# taillights3.net
KiCad netlist of a schematic drawn in EAGLE
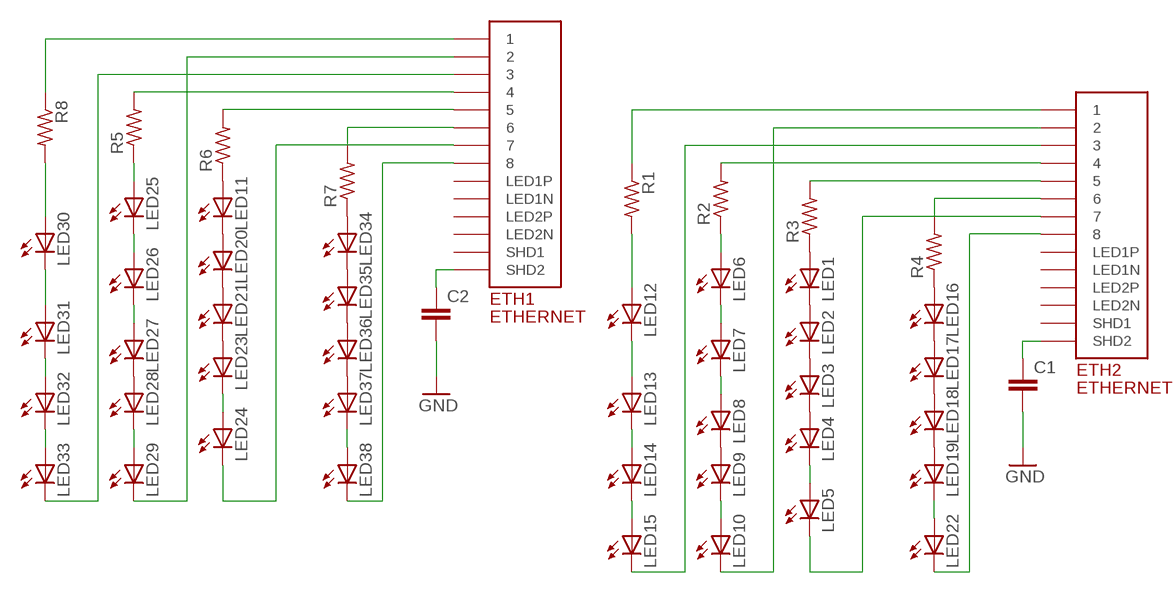
[diagram p0: schematic, sheet 1]

(export (version "E")
  (design (tool "Eeschema 10.0.6"))
  (components
    (comp (ref "C1")
      (value "C2,5-3")
      (footprint "eagle-import:C2.5-3")
      (libsource (lib "eagle-import") (part "C2,5-3"))
    )
    (comp (ref "C2")
      (value "C2,5-3")
      (footprint "eagle-import:C2.5-3")
      (libsource (lib "eagle-import") (part "C2,5-3"))
    )
    (comp (ref "ETH1")
      (value "ETHERNET")
      (footprint "eagle-import:A122645-ND")
      (libsource (lib "eagle-import") (part "ETHERNET"))
    )
    (comp (ref "ETH2")
      (value "ETHERNET")
      (footprint "eagle-import:A122645-ND")
      (libsource (lib "eagle-import") (part "ETHERNET"))
    )
    (comp (ref "LED1")
      (value "LED")
      (footprint "eagle-import:SMARTLED-TTW")
      (libsource (lib "eagle-import") (part "LED"))
    )
    (comp (ref "LED2")
      (value "LED")
      (footprint "eagle-import:SMARTLED-TTW")
      (libsource (lib "eagle-import") (part "LED"))
    )
    (comp (ref "LED3")
      (value "LED")
      (footprint "eagle-import:SMARTLED-TTW")
      (libsource (lib "eagle-import") (part "LED"))
    )
    (comp (ref "LED4")
      (value "LED")
      (footprint "eagle-import:SMARTLED-TTW")
      (libsource (lib "eagle-import") (part "LED"))
    )
    (comp (ref "LED5")
      (value "LED")
      (footprint "eagle-import:SMARTLED-TTW")
      (libsource (lib "eagle-import") (part "LED"))
    )
    (comp (ref "LED6")
      (value "LED")
      (footprint "eagle-import:SMARTLED-TTW")
      (libsource (lib "eagle-import") (part "LED"))
    )
    (comp (ref "LED7")
      (value "LED")
      (footprint "eagle-import:SMARTLED-TTW")
      (libsource (lib "eagle-import") (part "LED"))
    )
    (comp (ref "LED8")
      (value "LED")
      (footprint "eagle-import:SMARTLED-TTW")
      (libsource (lib "eagle-import") (part "LED"))
    )
    (comp (ref "LED9")
      (value "LED")
      (footprint "eagle-import:SMARTLED-TTW")
      (libsource (lib "eagle-import") (part "LED"))
    )
    (comp (ref "LED10")
      (value "LED")
      (footprint "eagle-import:SMARTLED-TTW")
      (libsource (lib "eagle-import") (part "LED"))
    )
    (comp (ref "LED11")
      (value "LED")
      (footprint "eagle-import:SMARTLED-TTW")
      (libsource (lib "eagle-import") (part "LED"))
    )
    (comp (ref "LED12")
      (value "LED")
      (footprint "eagle-import:SMARTLED-TTW")
      (libsource (lib "eagle-import") (part "LED"))
    )
    (comp (ref "LED13")
      (value "LED")
      (footprint "eagle-import:SMARTLED-TTW")
      (libsource (lib "eagle-import") (part "LED"))
    )
    (comp (ref "LED14")
      (value "LED")
      (footprint "eagle-import:SMARTLED-TTW")
      (libsource (lib "eagle-import") (part "LED"))
    )
    (comp (ref "LED15")
      (value "LED")
      (footprint "eagle-import:SMARTLED-TTW")
      (libsource (lib "eagle-import") (part "LED"))
    )
    (comp (ref "LED16")
      (value "LED")
      (footprint "eagle-import:SMARTLED-TTW")
      (libsource (lib "eagle-import") (part "LED"))
    )
    (comp (ref "LED17")
      (value "LED")
      (footprint "eagle-import:SMARTLED-TTW")
      (libsource (lib "eagle-import") (part "LED"))
    )
    (comp (ref "LED18")
      (value "LED")
      (footprint "eagle-import:SMARTLED-TTW")
      (libsource (lib "eagle-import") (part "LED"))
    )
    (comp (ref "LED19")
      (value "LED")
      (footprint "eagle-import:SMARTLED-TTW")
      (libsource (lib "eagle-import") (part "LED"))
    )
    (comp (ref "LED20")
      (value "LED")
      (footprint "eagle-import:SMARTLED-TTW")
      (libsource (lib "eagle-import") (part "LED"))
    )
    (comp (ref "LED21")
      (value "LED")
      (footprint "eagle-import:SMARTLED-TTW")
      (libsource (lib "eagle-import") (part "LED"))
    )
    (comp (ref "LED22")
      (value "LED")
      (footprint "eagle-import:SMARTLED-TTW")
      (libsource (lib "eagle-import") (part "LED"))
    )
    (comp (ref "LED23")
      (value "LED")
      (footprint "eagle-import:SMARTLED-TTW")
      (libsource (lib "eagle-import") (part "LED"))
    )
    (comp (ref "LED24")
      (value "LED")
      (footprint "eagle-import:SMARTLED-TTW")
      (libsource (lib "eagle-import") (part "LED"))
    )
    (comp (ref "LED25")
      (value "LED")
      (footprint "eagle-import:SMARTLED-TTW")
      (libsource (lib "eagle-import") (part "LED"))
    )
    (comp (ref "LED26")
      (value "LED")
      (footprint "eagle-import:SMARTLED-TTW")
      (libsource (lib "eagle-import") (part "LED"))
    )
    (comp (ref "LED27")
      (value "LED")
      (footprint "eagle-import:SMARTLED-TTW")
      (libsource (lib "eagle-import") (part "LED"))
    )
    (comp (ref "LED28")
      (value "LED")
      (footprint "eagle-import:SMARTLED-TTW")
      (libsource (lib "eagle-import") (part "LED"))
    )
    (comp (ref "LED29")
      (value "LED")
      (footprint "eagle-import:SMARTLED-TTW")
      (libsource (lib "eagle-import") (part "LED"))
    )
    (comp (ref "LED30")
      (value "LED")
      (footprint "eagle-import:SMARTLED-TTW")
      (libsource (lib "eagle-import") (part "LED"))
    )
    (comp (ref "LED31")
      (value "LED")
      (footprint "eagle-import:SMARTLED-TTW")
      (libsource (lib "eagle-import") (part "LED"))
    )
    (comp (ref "LED32")
      (value "LED")
      (footprint "eagle-import:SMARTLED-TTW")
      (libsource (lib "eagle-import") (part "LED"))
    )
    (comp (ref "LED33")
      (value "LED")
      (footprint "eagle-import:SMARTLED-TTW")
      (libsource (lib "eagle-import") (part "LED"))
    )
    (comp (ref "LED34")
      (value "LED")
      (footprint "eagle-import:SMARTLED-TTW")
      (libsource (lib "eagle-import") (part "LED"))
    )
    (comp (ref "LED35")
      (value "LED")
      (footprint "eagle-import:SMARTLED-TTW")
      (libsource (lib "eagle-import") (part "LED"))
    )
    (comp (ref "LED36")
      (value "LED")
      (footprint "eagle-import:SMARTLED-TTW")
      (libsource (lib "eagle-import") (part "LED"))
    )
    (comp (ref "LED37")
      (value "LED")
      (footprint "eagle-import:SMARTLED-TTW")
      (libsource (lib "eagle-import") (part "LED"))
    )
    (comp (ref "LED38")
      (value "LED")
      (footprint "eagle-import:SMARTLED-TTW")
      (libsource (lib "eagle-import") (part "LED"))
    )
    (comp (ref "R1")
      (value "R-US_0204/5")
      (footprint "eagle-import:0204_5")
      (libsource (lib "eagle-import") (part "R-US_0204/5"))
    )
    (comp (ref "R2")
      (value "R-US_0204/2V")
      (footprint "eagle-import:0204V")
      (libsource (lib "eagle-import") (part "R-US_0204/2V"))
    )
    (comp (ref "R3")
      (value "R-US_0204/2V")
      (footprint "eagle-import:0204V")
      (libsource (lib "eagle-import") (part "R-US_0204/2V"))
    )
    (comp (ref "R4")
      (value "R-US_0204/2V")
      (footprint "eagle-import:0204V")
      (libsource (lib "eagle-import") (part "R-US_0204/2V"))
    )
    (comp (ref "R5")
      (value "R-US_0204/2V")
      (footprint "eagle-import:0204V")
      (libsource (lib "eagle-import") (part "R-US_0204/2V"))
    )
    (comp (ref "R6")
      (value "R-US_0204/2V")
      (footprint "eagle-import:0204V")
      (libsource (lib "eagle-import") (part "R-US_0204/2V"))
    )
    (comp (ref "R7")
      (value "R-US_0204/2V")
      (footprint "eagle-import:0204V")
      (libsource (lib "eagle-import") (part "R-US_0204/2V"))
    )
    (comp (ref "R8")
      (value "R-US_0204/5")
      (footprint "eagle-import:0204_5")
      (libsource (lib "eagle-import") (part "R-US_0204/5"))
    )
  )
  (nets
    (net (code "1") (name "GND") (class "Default")
      (node (ref "C1") (pin "2") (pinfunction "2_2") (pintype "passive"))
      (node (ref "C2") (pin "2") (pinfunction "2_2") (pintype "passive"))
    )
    (net (code "2") (name "Net-(ETH1-1)") (class "Default")
      (node (ref "ETH1") (pin "P$1") (pinfunction "1_P$1") (pintype "bidirectional"))
      (node (ref "R8") (pin "1") (pinfunction "1_1") (pintype "passive"))
    )
    (net (code "3") (name "Net-(ETH1-2)") (class "Default")
      (node (ref "ETH1") (pin "P$2") (pinfunction "2_P$2") (pintype "bidirectional"))
      (node (ref "LED29") (pin "C@1") (pinfunction "C_C@1") (pintype "passive"))
    )
    (net (code "4") (name "Net-(ETH1-3)") (class "Default")
      (node (ref "ETH1") (pin "P$3") (pinfunction "3_P$3") (pintype "bidirectional"))
      (node (ref "LED33") (pin "C@1") (pinfunction "C_C@1") (pintype "passive"))
    )
    (net (code "5") (name "Net-(ETH1-4)") (class "Default")
      (node (ref "ETH1") (pin "P$4") (pinfunction "4_P$4") (pintype "bidirectional"))
      (node (ref "R5") (pin "2") (pinfunction "2_2") (pintype "passive"))
    )
    (net (code "6") (name "Net-(ETH1-5)") (class "Default")
      (node (ref "ETH1") (pin "P$5") (pinfunction "5_P$5") (pintype "bidirectional"))
      (node (ref "R6") (pin "2") (pinfunction "2_2") (pintype "passive"))
    )
    (net (code "7") (name "Net-(ETH1-6)") (class "Default")
      (node (ref "ETH1") (pin "P$6") (pinfunction "6_P$6") (pintype "bidirectional"))
      (node (ref "R7") (pin "2") (pinfunction "2_2") (pintype "passive"))
    )
    (net (code "8") (name "Net-(ETH1-7)") (class "Default")
      (node (ref "ETH1") (pin "P$7") (pinfunction "7_P$7") (pintype "bidirectional"))
      (node (ref "LED24") (pin "C@1") (pinfunction "C_C@1") (pintype "passive"))
    )
    (net (code "9") (name "Net-(ETH1-8)") (class "Default")
      (node (ref "ETH1") (pin "P$8") (pinfunction "8_P$8") (pintype "bidirectional"))
      (node (ref "LED38") (pin "C@1") (pinfunction "C_C@1") (pintype "passive"))
    )
    (net (code "10") (name "Net-(ETH1-SHD2)") (class "Default")
      (node (ref "C2") (pin "1") (pinfunction "1_1") (pintype "passive"))
      (node (ref "ETH1") (pin "P$14") (pinfunction "SHD2_P$14") (pintype "bidirectional"))
    )
    (net (code "11") (name "Net-(ETH2-1)") (class "Default")
      (node (ref "ETH2") (pin "P$1") (pinfunction "1_P$1") (pintype "bidirectional"))
      (node (ref "R1") (pin "1") (pinfunction "1_1") (pintype "passive"))
    )
    (net (code "12") (name "Net-(ETH2-2)") (class "Default")
      (node (ref "ETH2") (pin "P$2") (pinfunction "2_P$2") (pintype "bidirectional"))
      (node (ref "LED10") (pin "C@1") (pinfunction "C_C@1") (pintype "passive"))
    )
    (net (code "13") (name "Net-(ETH2-3)") (class "Default")
      (node (ref "ETH2") (pin "P$3") (pinfunction "3_P$3") (pintype "bidirectional"))
      (node (ref "LED15") (pin "C@1") (pinfunction "C_C@1") (pintype "passive"))
    )
    (net (code "14") (name "Net-(ETH2-4)") (class "Default")
      (node (ref "ETH2") (pin "P$4") (pinfunction "4_P$4") (pintype "bidirectional"))
      (node (ref "R2") (pin "2") (pinfunction "2_2") (pintype "passive"))
    )
    (net (code "15") (name "Net-(ETH2-5)") (class "Default")
      (node (ref "ETH2") (pin "P$5") (pinfunction "5_P$5") (pintype "bidirectional"))
      (node (ref "R3") (pin "2") (pinfunction "2_2") (pintype "passive"))
    )
    (net (code "16") (name "Net-(ETH2-6)") (class "Default")
      (node (ref "ETH2") (pin "P$6") (pinfunction "6_P$6") (pintype "bidirectional"))
      (node (ref "R4") (pin "2") (pinfunction "2_2") (pintype "passive"))
    )
    (net (code "17") (name "Net-(ETH2-7)") (class "Default")
      (node (ref "ETH2") (pin "P$7") (pinfunction "7_P$7") (pintype "bidirectional"))
      (node (ref "LED5") (pin "C@1") (pinfunction "C_C@1") (pintype "passive"))
    )
    (net (code "18") (name "Net-(ETH2-8)") (class "Default")
      (node (ref "ETH2") (pin "P$8") (pinfunction "8_P$8") (pintype "bidirectional"))
      (node (ref "LED22") (pin "C@1") (pinfunction "C_C@1") (pintype "passive"))
    )
    (net (code "19") (name "Net-(ETH2-SHD2)") (class "Default")
      (node (ref "C1") (pin "1") (pinfunction "1_1") (pintype "passive"))
      (node (ref "ETH2") (pin "P$14") (pinfunction "SHD2_P$14") (pintype "bidirectional"))
    )
    (net (code "20") (name "Net-(LED1-A)") (class "Default")
      (node (ref "LED1") (pin "A@1") (pinfunction "A_A@1") (pintype "passive"))
      (node (ref "R3") (pin "1") (pinfunction "1_1") (pintype "passive"))
    )
    (net (code "21") (name "Net-(LED1-C)") (class "Default")
      (node (ref "LED1") (pin "C@1") (pinfunction "C_C@1") (pintype "passive"))
      (node (ref "LED2") (pin "A@1") (pinfunction "A_A@1") (pintype "passive"))
    )
    (net (code "22") (name "Net-(LED2-C)") (class "Default")
      (node (ref "LED2") (pin "C@1") (pinfunction "C_C@1") (pintype "passive"))
      (node (ref "LED3") (pin "A@1") (pinfunction "A_A@1") (pintype "passive"))
    )
    (net (code "23") (name "Net-(LED3-C)") (class "Default")
      (node (ref "LED3") (pin "C@1") (pinfunction "C_C@1") (pintype "passive"))
      (node (ref "LED4") (pin "A@1") (pinfunction "A_A@1") (pintype "passive"))
    )
    (net (code "24") (name "Net-(LED4-C)") (class "Default")
      (node (ref "LED4") (pin "C@1") (pinfunction "C_C@1") (pintype "passive"))
      (node (ref "LED5") (pin "A@1") (pinfunction "A_A@1") (pintype "passive"))
    )
    (net (code "25") (name "Net-(LED6-A)") (class "Default")
      (node (ref "LED6") (pin "A@1") (pinfunction "A_A@1") (pintype "passive"))
      (node (ref "R2") (pin "1") (pinfunction "1_1") (pintype "passive"))
    )
    (net (code "26") (name "Net-(LED6-C)") (class "Default")
      (node (ref "LED6") (pin "C@1") (pinfunction "C_C@1") (pintype "passive"))
      (node (ref "LED7") (pin "A@1") (pinfunction "A_A@1") (pintype "passive"))
    )
    (net (code "27") (name "Net-(LED7-C)") (class "Default")
      (node (ref "LED7") (pin "C@1") (pinfunction "C_C@1") (pintype "passive"))
      (node (ref "LED8") (pin "A@1") (pinfunction "A_A@1") (pintype "passive"))
    )
    (net (code "28") (name "Net-(LED8-C)") (class "Default")
      (node (ref "LED8") (pin "C@1") (pinfunction "C_C@1") (pintype "passive"))
      (node (ref "LED9") (pin "A@1") (pinfunction "A_A@1") (pintype "passive"))
    )
    (net (code "29") (name "Net-(LED10-A)") (class "Default")
      (node (ref "LED10") (pin "A@1") (pinfunction "A_A@1") (pintype "passive"))
      (node (ref "LED9") (pin "C@1") (pinfunction "C_C@1") (pintype "passive"))
    )
    (net (code "30") (name "Net-(LED11-A)") (class "Default")
      (node (ref "LED11") (pin "A@1") (pinfunction "A_A@1") (pintype "passive"))
      (node (ref "R6") (pin "1") (pinfunction "1_1") (pintype "passive"))
    )
    (net (code "31") (name "Net-(LED11-C)") (class "Default")
      (node (ref "LED11") (pin "C@1") (pinfunction "C_C@1") (pintype "passive"))
      (node (ref "LED20") (pin "A@1") (pinfunction "A_A@1") (pintype "passive"))
    )
    (net (code "32") (name "Net-(LED12-A)") (class "Default")
      (node (ref "LED12") (pin "A@1") (pinfunction "A_A@1") (pintype "passive"))
      (node (ref "R1") (pin "2") (pinfunction "2_2") (pintype "passive"))
    )
    (net (code "33") (name "Net-(LED12-C)") (class "Default")
      (node (ref "LED12") (pin "C@1") (pinfunction "C_C@1") (pintype "passive"))
      (node (ref "LED13") (pin "A@1") (pinfunction "A_A@1") (pintype "passive"))
    )
    (net (code "34") (name "Net-(LED13-C)") (class "Default")
      (node (ref "LED13") (pin "C@1") (pinfunction "C_C@1") (pintype "passive"))
      (node (ref "LED14") (pin "A@1") (pinfunction "A_A@1") (pintype "passive"))
    )
    (net (code "35") (name "Net-(LED14-C)") (class "Default")
      (node (ref "LED14") (pin "C@1") (pinfunction "C_C@1") (pintype "passive"))
      (node (ref "LED15") (pin "A@1") (pinfunction "A_A@1") (pintype "passive"))
    )
    (net (code "36") (name "Net-(LED16-A)") (class "Default")
      (node (ref "LED16") (pin "A@1") (pinfunction "A_A@1") (pintype "passive"))
      (node (ref "R4") (pin "1") (pinfunction "1_1") (pintype "passive"))
    )
    (net (code "37") (name "Net-(LED16-C)") (class "Default")
      (node (ref "LED16") (pin "C@1") (pinfunction "C_C@1") (pintype "passive"))
      (node (ref "LED17") (pin "A@1") (pinfunction "A_A@1") (pintype "passive"))
    )
    (net (code "38") (name "Net-(LED17-C)") (class "Default")
      (node (ref "LED17") (pin "C@1") (pinfunction "C_C@1") (pintype "passive"))
      (node (ref "LED18") (pin "A@1") (pinfunction "A_A@1") (pintype "passive"))
    )
    (net (code "39") (name "Net-(LED18-C)") (class "Default")
      (node (ref "LED18") (pin "C@1") (pinfunction "C_C@1") (pintype "passive"))
      (node (ref "LED19") (pin "A@1") (pinfunction "A_A@1") (pintype "passive"))
    )
    (net (code "40") (name "Net-(LED19-C)") (class "Default")
      (node (ref "LED19") (pin "C@1") (pinfunction "C_C@1") (pintype "passive"))
      (node (ref "LED22") (pin "A@1") (pinfunction "A_A@1") (pintype "passive"))
    )
    (net (code "41") (name "Net-(LED20-C)") (class "Default")
      (node (ref "LED20") (pin "C@1") (pinfunction "C_C@1") (pintype "passive"))
      (node (ref "LED21") (pin "A@1") (pinfunction "A_A@1") (pintype "passive"))
    )
    (net (code "42") (name "Net-(LED21-C)") (class "Default")
      (node (ref "LED21") (pin "C@1") (pinfunction "C_C@1") (pintype "passive"))
      (node (ref "LED23") (pin "A@1") (pinfunction "A_A@1") (pintype "passive"))
    )
    (net (code "43") (name "Net-(LED23-C)") (class "Default")
      (node (ref "LED23") (pin "C@1") (pinfunction "C_C@1") (pintype "passive"))
      (node (ref "LED24") (pin "A@1") (pinfunction "A_A@1") (pintype "passive"))
    )
    (net (code "44") (name "Net-(LED25-A)") (class "Default")
      (node (ref "LED25") (pin "A@1") (pinfunction "A_A@1") (pintype "passive"))
      (node (ref "R5") (pin "1") (pinfunction "1_1") (pintype "passive"))
    )
    (net (code "45") (name "Net-(LED25-C)") (class "Default")
      (node (ref "LED25") (pin "C@1") (pinfunction "C_C@1") (pintype "passive"))
      (node (ref "LED26") (pin "A@1") (pinfunction "A_A@1") (pintype "passive"))
    )
    (net (code "46") (name "Net-(LED26-C)") (class "Default")
      (node (ref "LED26") (pin "C@1") (pinfunction "C_C@1") (pintype "passive"))
      (node (ref "LED27") (pin "A@1") (pinfunction "A_A@1") (pintype "passive"))
    )
    (net (code "47") (name "Net-(LED27-C)") (class "Default")
      (node (ref "LED27") (pin "C@1") (pinfunction "C_C@1") (pintype "passive"))
      (node (ref "LED28") (pin "A@1") (pinfunction "A_A@1") (pintype "passive"))
    )
    (net (code "48") (name "Net-(LED28-C)") (class "Default")
      (node (ref "LED28") (pin "C@1") (pinfunction "C_C@1") (pintype "passive"))
      (node (ref "LED29") (pin "A@1") (pinfunction "A_A@1") (pintype "passive"))
    )
    (net (code "49") (name "Net-(LED30-A)") (class "Default")
      (node (ref "LED30") (pin "A@1") (pinfunction "A_A@1") (pintype "passive"))
      (node (ref "R8") (pin "2") (pinfunction "2_2") (pintype "passive"))
    )
    (net (code "50") (name "Net-(LED30-C)") (class "Default")
      (node (ref "LED30") (pin "C@1") (pinfunction "C_C@1") (pintype "passive"))
      (node (ref "LED31") (pin "A@1") (pinfunction "A_A@1") (pintype "passive"))
    )
    (net (code "51") (name "Net-(LED31-C)") (class "Default")
      (node (ref "LED31") (pin "C@1") (pinfunction "C_C@1") (pintype "passive"))
      (node (ref "LED32") (pin "A@1") (pinfunction "A_A@1") (pintype "passive"))
    )
    (net (code "52") (name "Net-(LED32-C)") (class "Default")
      (node (ref "LED32") (pin "C@1") (pinfunction "C_C@1") (pintype "passive"))
      (node (ref "LED33") (pin "A@1") (pinfunction "A_A@1") (pintype "passive"))
    )
    (net (code "53") (name "Net-(LED34-A)") (class "Default")
      (node (ref "LED34") (pin "A@1") (pinfunction "A_A@1") (pintype "passive"))
      (node (ref "R7") (pin "1") (pinfunction "1_1") (pintype "passive"))
    )
    (net (code "54") (name "Net-(LED34-C)") (class "Default")
      (node (ref "LED34") (pin "C@1") (pinfunction "C_C@1") (pintype "passive"))
      (node (ref "LED35") (pin "A@1") (pinfunction "A_A@1") (pintype "passive"))
    )
    (net (code "55") (name "Net-(LED35-C)") (class "Default")
      (node (ref "LED35") (pin "C@1") (pinfunction "C_C@1") (pintype "passive"))
      (node (ref "LED36") (pin "A@1") (pinfunction "A_A@1") (pintype "passive"))
    )
    (net (code "56") (name "Net-(LED36-C)") (class "Default")
      (node (ref "LED36") (pin "C@1") (pinfunction "C_C@1") (pintype "passive"))
      (node (ref "LED37") (pin "A@1") (pinfunction "A_A@1") (pintype "passive"))
    )
    (net (code "57") (name "Net-(LED37-C)") (class "Default")
      (node (ref "LED37") (pin "C@1") (pinfunction "C_C@1") (pintype "passive"))
      (node (ref "LED38") (pin "A@1") (pinfunction "A_A@1") (pintype "passive"))
    )
    (net (code "58") (name "unconnected-(ETH1-LED1N-PadP$9)") (class "Default")
      (node (ref "ETH1") (pin "P$9") (pinfunction "LED1N_P$9") (pintype "bidirectional"))
    )
    (net (code "59") (name "unconnected-(ETH1-LED1P-PadP$10)") (class "Default")
      (node (ref "ETH1") (pin "P$10") (pinfunction "LED1P_P$10") (pintype "bidirectional"))
    )
    (net (code "60") (name "unconnected-(ETH1-LED2N-PadP$11)") (class "Default")
      (node (ref "ETH1") (pin "P$11") (pinfunction "LED2N_P$11") (pintype "bidirectional"))
    )
    (net (code "61") (name "unconnected-(ETH1-LED2P-PadP$12)") (class "Default")
      (node (ref "ETH1") (pin "P$12") (pinfunction "LED2P_P$12") (pintype "bidirectional"))
    )
    (net (code "62") (name "unconnected-(ETH1-SHD1-PadP$13)") (class "Default")
      (node (ref "ETH1") (pin "P$13") (pinfunction "SHD1_P$13") (pintype "bidirectional"))
    )
    (net (code "63") (name "unconnected-(ETH2-LED1N-PadP$9)") (class "Default")
      (node (ref "ETH2") (pin "P$9") (pinfunction "LED1N_P$9") (pintype "bidirectional"))
    )
    (net (code "64") (name "unconnected-(ETH2-LED1P-PadP$10)") (class "Default")
      (node (ref "ETH2") (pin "P$10") (pinfunction "LED1P_P$10") (pintype "bidirectional"))
    )
    (net (code "65") (name "unconnected-(ETH2-LED2N-PadP$11)") (class "Default")
      (node (ref "ETH2") (pin "P$11") (pinfunction "LED2N_P$11") (pintype "bidirectional"))
    )
    (net (code "66") (name "unconnected-(ETH2-LED2P-PadP$12)") (class "Default")
      (node (ref "ETH2") (pin "P$12") (pinfunction "LED2P_P$12") (pintype "bidirectional"))
    )
    (net (code "67") (name "unconnected-(ETH2-SHD1-PadP$13)") (class "Default")
      (node (ref "ETH2") (pin "P$13") (pinfunction "SHD1_P$13") (pintype "bidirectional"))
    )
  )
)
